# TinyISD1700_V2_2020-08-19-smd-sop-1206.net
KiCad netlist of a schematic drawn in EAGLE
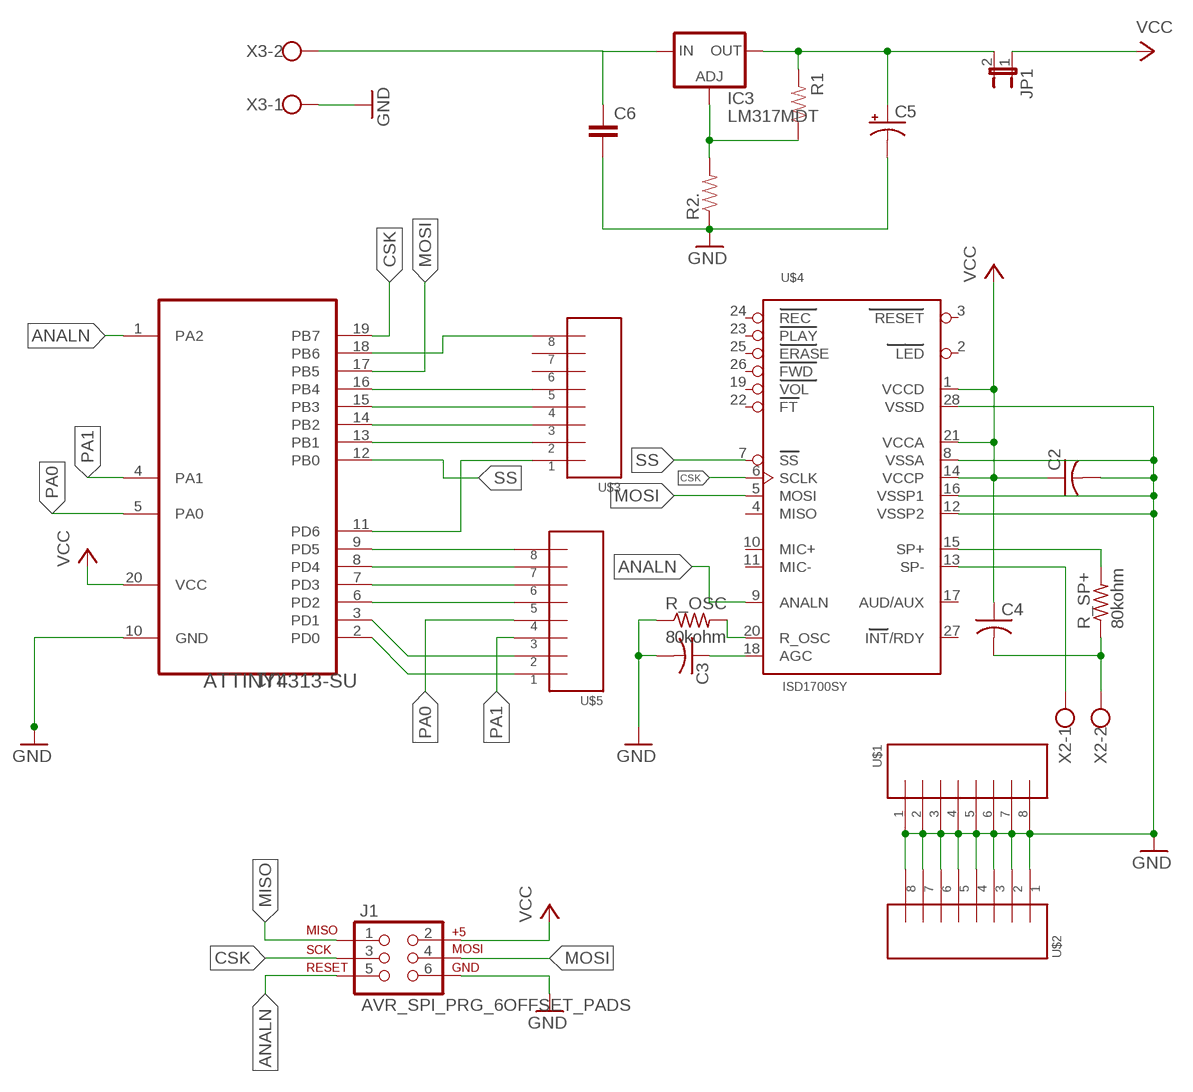
[diagram p0: schematic, sheet 1]

(export (version "E")
  (design (tool "Eeschema 10.0.6"))
  (components
    (comp (ref "C2")
      (value "C-US050-030X075")
      (footprint "eagle-import:C050-030X075")
      (libsource (lib "eagle-import") (part "C-US050-030X075"))
    )
    (comp (ref "C3")
      (value "C-US050-030X075")
      (footprint "eagle-import:C050-030X075")
      (libsource (lib "eagle-import") (part "C-US050-030X075"))
    )
    (comp (ref "C4")
      (value "C-US050-030X075")
      (footprint "eagle-import:C050-030X075")
      (libsource (lib "eagle-import") (part "C-US050-030X075"))
    )
    (comp (ref "C5")
      (value "CAP_POL1206")
      (footprint "eagle-import:EIA3216")
      (libsource (lib "eagle-import") (part "CAP_POL1206"))
    )
    (comp (ref "C6")
      (value "CAP0805")
      (footprint "eagle-import:0805")
      (libsource (lib "eagle-import") (part "CAP0805"))
    )
    (comp (ref "IC3")
      (value "LM317MDT")
      (footprint "eagle-import:DPACK")
      (libsource (lib "eagle-import") (part "LM317?MDT"))
    )
    (comp (ref "J1")
      (value "AVR_SPI_PRG_6OFFSET_PADS")
      (footprint "eagle-import:2X3_OFFSET")
      (libsource (lib "eagle-import") (part "AVR_SPI_PRG_6OFFSET_PADS"))
    )
    (comp (ref "JP1")
      (value "JP1E")
      (footprint "eagle-import:JP1")
      (libsource (lib "eagle-import") (part "JP1E"))
    )
    (comp (ref "R1")
      (value "RESISTOR")
      (footprint "eagle-import:0805")
      (libsource (lib "eagle-import") (part "RESISTOR"))
    )
    (comp (ref "R2.")
      (value "RESISTOR")
      (footprint "eagle-import:0805")
      (libsource (lib "eagle-import") (part "RESISTOR"))
    )
    (comp (ref "R_OSC")
      (value "80kohm")
      (footprint "eagle-import:0204V")
      (libsource (lib "eagle-import") (part "R-US_0204/2V"))
    )
    (comp (ref "R_SP+")
      (value "80kohm")
      (footprint "eagle-import:0204V")
      (libsource (lib "eagle-import") (part "R-US_0204/2V"))
    )
    (comp (ref "U$1")
      (value "8PIN_HEADER")
      (footprint "eagle-import:8PIN_HEADER")
      (fields (field (name "MF") "RENESAS") (field (name "MPN") "YSDKS128E10"))
      (libsource (lib "eagle-import") (part "8PIN_HEADER"))
    )
    (comp (ref "U$2")
      (value "8PIN_HEADER")
      (footprint "eagle-import:8PIN_HEADER")
      (fields (field (name "MF") "RENESAS") (field (name "MPN") "YSDKS128E10"))
      (libsource (lib "eagle-import") (part "8PIN_HEADER"))
    )
    (comp (ref "U$3")
      (value "8PIN_HEADER")
      (footprint "eagle-import:8PIN_HEADER")
      (fields (field (name "MF") "RENESAS") (field (name "MPN") "YSDKS128E10"))
      (libsource (lib "eagle-import") (part "8PIN_HEADER"))
    )
    (comp (ref "U$4")
      (value "ISD1700SY")
      (footprint "eagle-import:SO28W")
      (libsource (lib "eagle-import") (part "ISD1700SY"))
    )
    (comp (ref "U$5")
      (value "8PIN_HEADER")
      (footprint "eagle-import:8PIN_HEADER")
      (fields (field (name "MF") "RENESAS") (field (name "MPN") "YSDKS128E10"))
      (libsource (lib "eagle-import") (part "8PIN_HEADER"))
    )
    (comp (ref "U1")
      (value "ATTINY4313-SU")
      (footprint "eagle-import:SOIC127P1032X265-20N")
      (fields (field (name "MF") "MICROCHIP"))
      (libsource (lib "eagle-import") (part "ATTINY4313-SU"))
    )
    (comp (ref "X2")
      (value "W237-102")
      (footprint "eagle-import:W237-102")
      (fields (field (name "MPN") "237-102"))
      (libsource (lib "eagle-import") (part "W237-102"))
    )
    (comp (ref "X3")
      (value "W237-102")
      (footprint "eagle-import:W237-102")
      (fields (field (name "MPN") "237-102") (field (name "OC_NEWARK") "70K9898"))
      (libsource (lib "eagle-import") (part "W237-102"))
    )
  )
  (nets
    (net (code "1") (name "ANALN") (class "Default")
      (node (ref "J1") (pin "5") (pinfunction "5_5") (pintype "passive"))
      (node (ref "U$4") (pin "9") (pinfunction "ANALN_9") (pintype "input"))
      (node (ref "U1") (pin "1") (pinfunction "PA2_1") (pintype "bidirectional"))
    )
    (net (code "2") (name "CSK") (class "Default")
      (node (ref "J1") (pin "3") (pinfunction "3_3") (pintype "passive"))
      (node (ref "U$4") (pin "6") (pinfunction "SCLK_6") (pintype "input"))
      (node (ref "U1") (pin "19") (pinfunction "PB7_19") (pintype "bidirectional"))
    )
    (net (code "3") (name "GND") (class "Default")
      (node (ref "C2") (pin "2") (pinfunction "2_2") (pintype "passive"))
      (node (ref "C3") (pin "2") (pinfunction "2_2") (pintype "passive"))
      (node (ref "C5") (pin "C") (pinfunction "-_C") (pintype "passive"))
      (node (ref "C6") (pin "2") (pinfunction "2_2") (pintype "passive"))
      (node (ref "J1") (pin "6") (pinfunction "6_6") (pintype "passive"))
      (node (ref "R2.") (pin "1") (pinfunction "1_1") (pintype "passive"))
      (node (ref "R_OSC") (pin "1") (pinfunction "1_1") (pintype "passive"))
      (node (ref "U$1") (pin "P$1") (pinfunction "P$1_P$1") (pintype "bidirectional"))
      (node (ref "U$1") (pin "P$2") (pinfunction "P$2_P$2") (pintype "bidirectional"))
      (node (ref "U$1") (pin "P$3") (pinfunction "P$3_P$3") (pintype "bidirectional"))
      (node (ref "U$1") (pin "P$4") (pinfunction "P$4_P$4") (pintype "bidirectional"))
      (node (ref "U$1") (pin "P$5") (pinfunction "P$5_P$5") (pintype "bidirectional"))
      (node (ref "U$1") (pin "P$6") (pinfunction "P$6_P$6") (pintype "bidirectional"))
      (node (ref "U$1") (pin "P$7") (pinfunction "P$7_P$7") (pintype "bidirectional"))
      (node (ref "U$1") (pin "P$8") (pinfunction "P$8_P$8") (pintype "bidirectional"))
      (node (ref "U$2") (pin "P$1") (pinfunction "P$1_P$1") (pintype "bidirectional"))
      (node (ref "U$2") (pin "P$2") (pinfunction "P$2_P$2") (pintype "bidirectional"))
      (node (ref "U$2") (pin "P$3") (pinfunction "P$3_P$3") (pintype "bidirectional"))
      (node (ref "U$2") (pin "P$4") (pinfunction "P$4_P$4") (pintype "bidirectional"))
      (node (ref "U$2") (pin "P$5") (pinfunction "P$5_P$5") (pintype "bidirectional"))
      (node (ref "U$2") (pin "P$6") (pinfunction "P$6_P$6") (pintype "bidirectional"))
      (node (ref "U$2") (pin "P$7") (pinfunction "P$7_P$7") (pintype "bidirectional"))
      (node (ref "U$2") (pin "P$8") (pinfunction "P$8_P$8") (pintype "bidirectional"))
      (node (ref "U$4") (pin "12") (pinfunction "VSSP2_12") (pintype "power_in"))
      (node (ref "U$4") (pin "16") (pinfunction "VSSP1_16") (pintype "power_in"))
      (node (ref "U$4") (pin "28") (pinfunction "VSSD_28") (pintype "power_in"))
      (node (ref "U$4") (pin "8") (pinfunction "VSSA_8") (pintype "power_in"))
      (node (ref "U1") (pin "10") (pinfunction "GND_10") (pintype "passive"))
      (node (ref "X3") (pin "1") (pinfunction "KL_1") (pintype "passive"))
    )
    (net (code "4") (name "MISO") (class "Default")
      (node (ref "J1") (pin "1") (pinfunction "1_1") (pintype "passive"))
    )
    (net (code "5") (name "MOSI") (class "Default")
      (node (ref "J1") (pin "4") (pinfunction "4_4") (pintype "passive"))
      (node (ref "U$4") (pin "5") (pinfunction "MOSI_5") (pintype "input"))
      (node (ref "U1") (pin "17") (pinfunction "PB5_17") (pintype "bidirectional"))
    )
    (net (code "6") (name "Net-(C5-+)") (class "Default")
      (node (ref "C5") (pin "A") (pinfunction "+_A") (pintype "passive"))
      (node (ref "IC3") (pin "4") (pinfunction "OUT_4") (pintype "passive"))
      (node (ref "JP1") (pin "2") (pinfunction "2_2") (pintype "passive"))
      (node (ref "R1") (pin "2") (pinfunction "2_2") (pintype "passive"))
    )
    (net (code "7") (name "Net-(IC3-ADJ)") (class "Default")
      (node (ref "IC3") (pin "1") (pinfunction "ADJ_1") (pintype "input"))
      (node (ref "R1") (pin "1") (pinfunction "1_1") (pintype "passive"))
      (node (ref "R2.") (pin "2") (pinfunction "2_2") (pintype "passive"))
    )
    (net (code "8") (name "Net-(IC3-IN)") (class "Default")
      (node (ref "C6") (pin "1") (pinfunction "1_1") (pintype "passive"))
      (node (ref "IC3") (pin "3") (pinfunction "IN_3") (pintype "input"))
      (node (ref "X3") (pin "2") (pinfunction "KL_2") (pintype "passive"))
    )
    (net (code "9") (name "Net-(U$4-AGC)") (class "Default")
      (node (ref "C3") (pin "1") (pinfunction "1_1") (pintype "passive"))
      (node (ref "U$4") (pin "18") (pinfunction "AGC_18") (pintype "passive"))
    )
    (net (code "10") (name "Net-(U$4-R_OSC)") (class "Default")
      (node (ref "R_OSC") (pin "2") (pinfunction "2_2") (pintype "passive"))
      (node (ref "U$4") (pin "20") (pinfunction "R_OSC_20") (pintype "passive"))
    )
    (net (code "11") (name "Net-(U$4-SP+)") (class "Default")
      (node (ref "R_SP+") (pin "2") (pinfunction "2_2") (pintype "passive"))
      (node (ref "U$4") (pin "15") (pinfunction "SP+_15") (pintype "output"))
    )
    (net (code "12") (name "Net-(U$4-SP-)") (class "Default")
      (node (ref "U$4") (pin "13") (pinfunction "SP-_13") (pintype "output"))
      (node (ref "X2") (pin "1") (pinfunction "KL_1") (pintype "passive"))
    )
    (net (code "13") (name "Net-(U1-PB1)") (class "Default")
      (node (ref "U$3") (pin "P$2") (pinfunction "P$2_P$2") (pintype "bidirectional"))
      (node (ref "U1") (pin "13") (pinfunction "PB1_13") (pintype "bidirectional"))
    )
    (net (code "14") (name "Net-(U1-PB2)") (class "Default")
      (node (ref "U$3") (pin "P$3") (pinfunction "P$3_P$3") (pintype "bidirectional"))
      (node (ref "U1") (pin "14") (pinfunction "PB2_14") (pintype "bidirectional"))
    )
    (net (code "15") (name "Net-(U1-PB3)") (class "Default")
      (node (ref "U$3") (pin "P$4") (pinfunction "P$4_P$4") (pintype "bidirectional"))
      (node (ref "U1") (pin "15") (pinfunction "PB3_15") (pintype "bidirectional"))
    )
    (net (code "16") (name "Net-(U1-PB4)") (class "Default")
      (node (ref "U$3") (pin "P$5") (pinfunction "P$5_P$5") (pintype "bidirectional"))
      (node (ref "U1") (pin "16") (pinfunction "PB4_16") (pintype "bidirectional"))
    )
    (net (code "17") (name "Net-(U1-PB6)") (class "Default")
      (node (ref "U$3") (pin "P$8") (pinfunction "P$8_P$8") (pintype "bidirectional"))
      (node (ref "U1") (pin "18") (pinfunction "PB6_18") (pintype "bidirectional"))
    )
    (net (code "18") (name "Net-(U1-PD0)") (class "Default")
      (node (ref "U$5") (pin "P$1") (pinfunction "P$1_P$1") (pintype "bidirectional"))
      (node (ref "U1") (pin "2") (pinfunction "PD0_2") (pintype "bidirectional"))
    )
    (net (code "19") (name "Net-(U1-PD1)") (class "Default")
      (node (ref "U$5") (pin "P$2") (pinfunction "P$2_P$2") (pintype "bidirectional"))
      (node (ref "U1") (pin "3") (pinfunction "PD1_3") (pintype "bidirectional"))
    )
    (net (code "20") (name "Net-(U1-PD2)") (class "Default")
      (node (ref "U$5") (pin "P$5") (pinfunction "P$5_P$5") (pintype "bidirectional"))
      (node (ref "U1") (pin "6") (pinfunction "PD2_6") (pintype "bidirectional"))
    )
    (net (code "21") (name "Net-(U1-PD3)") (class "Default")
      (node (ref "U$5") (pin "P$6") (pinfunction "P$6_P$6") (pintype "bidirectional"))
      (node (ref "U1") (pin "7") (pinfunction "PD3_7") (pintype "bidirectional"))
    )
    (net (code "22") (name "Net-(U1-PD4)") (class "Default")
      (node (ref "U$5") (pin "P$7") (pinfunction "P$7_P$7") (pintype "bidirectional"))
      (node (ref "U1") (pin "8") (pinfunction "PD4_8") (pintype "bidirectional"))
    )
    (net (code "23") (name "Net-(U1-PD5)") (class "Default")
      (node (ref "U$5") (pin "P$8") (pinfunction "P$8_P$8") (pintype "bidirectional"))
      (node (ref "U1") (pin "9") (pinfunction "PD5_9") (pintype "bidirectional"))
    )
    (net (code "24") (name "Net-(U1-PD6)") (class "Default")
      (node (ref "U$3") (pin "P$1") (pinfunction "P$1_P$1") (pintype "bidirectional"))
      (node (ref "U1") (pin "11") (pinfunction "PD6_11") (pintype "bidirectional"))
    )
    (net (code "25") (name "Net-(X2B-KL)") (class "Default")
      (node (ref "C4") (pin "2") (pinfunction "2_2") (pintype "passive"))
      (node (ref "R_SP+") (pin "1") (pinfunction "1_1") (pintype "passive"))
      (node (ref "X2") (pin "2") (pinfunction "KL_2") (pintype "passive"))
    )
    (net (code "26") (name "PA0") (class "Default")
      (node (ref "U$5") (pin "P$4") (pinfunction "P$4_P$4") (pintype "bidirectional"))
      (node (ref "U1") (pin "5") (pinfunction "PA0_5") (pintype "bidirectional"))
    )
    (net (code "27") (name "PA1") (class "Default")
      (node (ref "U$5") (pin "P$3") (pinfunction "P$3_P$3") (pintype "bidirectional"))
      (node (ref "U1") (pin "4") (pinfunction "PA1_4") (pintype "bidirectional"))
    )
    (net (code "28") (name "SS") (class "Default")
      (node (ref "U$4") (pin "7") (pinfunction "SS_7") (pintype "input"))
      (node (ref "U1") (pin "12") (pinfunction "PB0_12") (pintype "bidirectional"))
    )
    (net (code "29") (name "VCC") (class "Default")
      (node (ref "C2") (pin "1") (pinfunction "1_1") (pintype "passive"))
      (node (ref "C4") (pin "1") (pinfunction "1_1") (pintype "passive"))
      (node (ref "J1") (pin "2") (pinfunction "2_2") (pintype "passive"))
      (node (ref "JP1") (pin "1") (pinfunction "1_1") (pintype "passive"))
      (node (ref "U$4") (pin "1") (pinfunction "VCCD_1") (pintype "power_in"))
      (node (ref "U$4") (pin "14") (pinfunction "VCCP_14") (pintype "power_in"))
      (node (ref "U$4") (pin "21") (pinfunction "VCCA_21") (pintype "power_in"))
      (node (ref "U1") (pin "20") (pinfunction "VCC_20") (pintype "power_in"))
    )
    (net (code "30") (name "unconnected-(U$3-PadP$6)") (class "Default")
      (node (ref "U$3") (pin "P$6") (pinfunction "P$6_P$6") (pintype "bidirectional"))
    )
    (net (code "31") (name "unconnected-(U$3-PadP$7)") (class "Default")
      (node (ref "U$3") (pin "P$7") (pinfunction "P$7_P$7") (pintype "bidirectional"))
    )
    (net (code "32") (name "unconnected-(U$4-AUD{slash}AUX-Pad17)") (class "Default")
      (node (ref "U$4") (pin "17") (pinfunction "AUD/AUX_17") (pintype "output"))
    )
    (net (code "33") (name "unconnected-(U$4-ERASE-Pad25)") (class "Default")
      (node (ref "U$4") (pin "25") (pinfunction "ERASE_25") (pintype "input"))
    )
    (net (code "34") (name "unconnected-(U$4-FT-Pad22)") (class "Default")
      (node (ref "U$4") (pin "22") (pinfunction "FT_22") (pintype "input"))
    )
    (net (code "35") (name "unconnected-(U$4-FWD-Pad26)") (class "Default")
      (node (ref "U$4") (pin "26") (pinfunction "FWD_26") (pintype "input"))
    )
    (net (code "36") (name "unconnected-(U$4-INT{slash}RDY-Pad27)") (class "Default")
      (node (ref "U$4") (pin "27") (pinfunction "INT/RDY_27") (pintype "bidirectional"))
    )
    (net (code "37") (name "unconnected-(U$4-LED-Pad2)") (class "Default")
      (node (ref "U$4") (pin "2") (pinfunction "LED_2") (pintype "input"))
    )
    (net (code "38") (name "unconnected-(U$4-MIC+-Pad10)") (class "Default")
      (node (ref "U$4") (pin "10") (pinfunction "MIC+_10") (pintype "input"))
    )
    (net (code "39") (name "unconnected-(U$4-MIC--Pad11)") (class "Default")
      (node (ref "U$4") (pin "11") (pinfunction "MIC-_11") (pintype "input"))
    )
    (net (code "40") (name "unconnected-(U$4-MISO-Pad4)") (class "Default")
      (node (ref "U$4") (pin "4") (pinfunction "MISO_4") (pintype "input"))
    )
    (net (code "41") (name "unconnected-(U$4-PLAY-Pad23)") (class "Default")
      (node (ref "U$4") (pin "23") (pinfunction "PLAY_23") (pintype "input"))
    )
    (net (code "42") (name "unconnected-(U$4-REC-Pad24)") (class "Default")
      (node (ref "U$4") (pin "24") (pinfunction "REC_24") (pintype "input"))
    )
    (net (code "43") (name "unconnected-(U$4-RESET-Pad3)") (class "Default")
      (node (ref "U$4") (pin "3") (pinfunction "RESET_3") (pintype "input"))
    )
    (net (code "44") (name "unconnected-(U$4-VOL-Pad19)") (class "Default")
      (node (ref "U$4") (pin "19") (pinfunction "VOL_19") (pintype "input"))
    )
  )
)
